# flextimus-prime.net
KiCad netlist of a schematic drawn in EAGLE
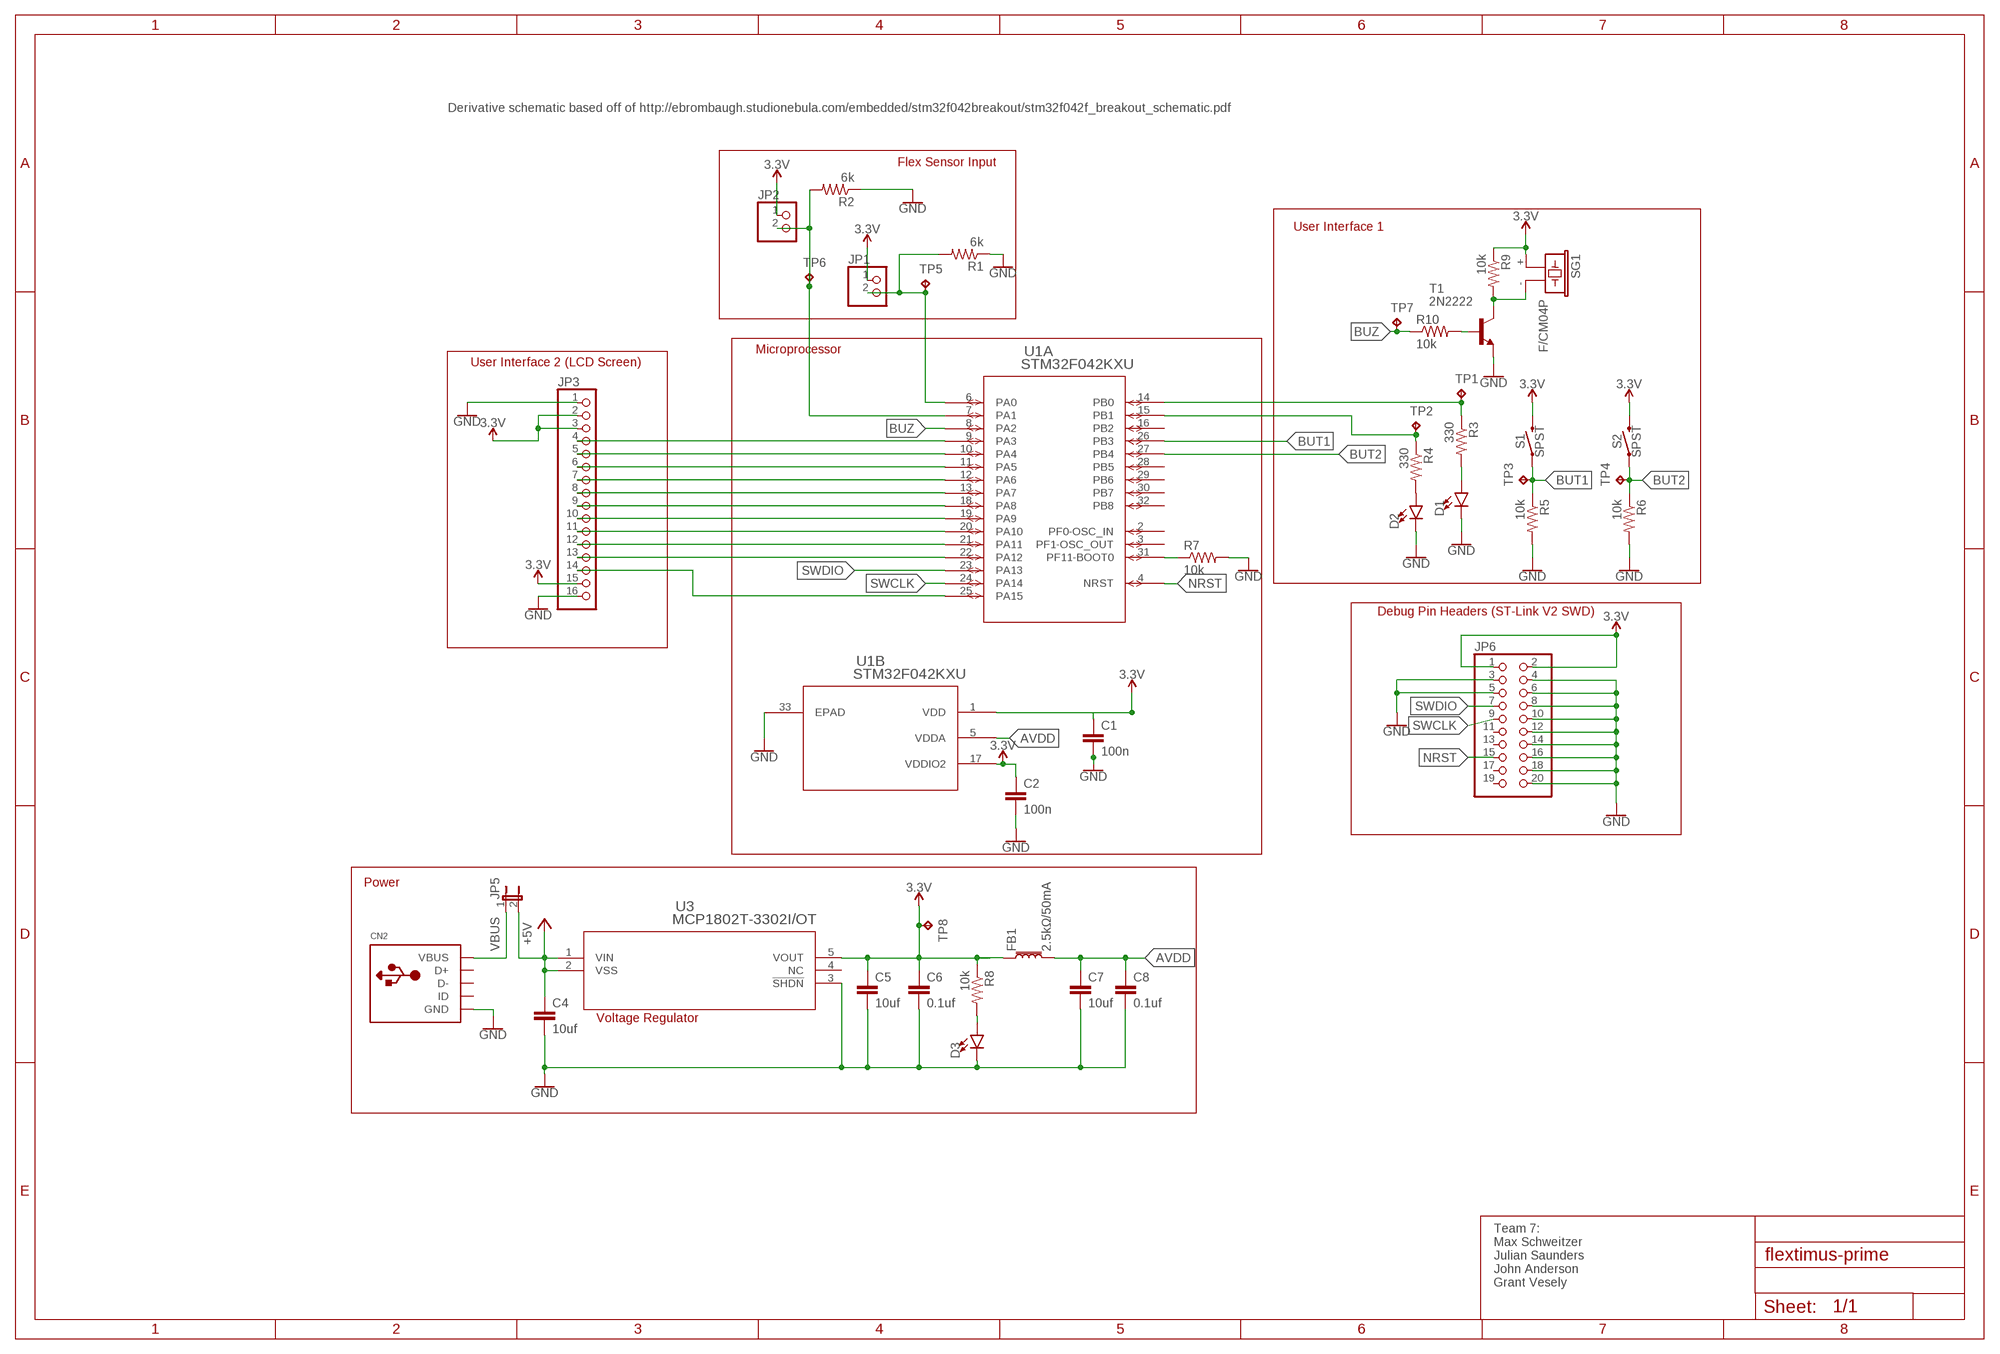
[diagram p0: schematic, sheet 1]

(export (version "E")
  (design (tool "Eeschema 10.0.6"))
  (components
    (comp (ref "C1")
      (value "100n")
      (footprint "eagle-import:C0805")
      (libsource (lib "eagle-import") (part "C-EUC0805"))
    )
    (comp (ref "C2")
      (value "100n")
      (footprint "eagle-import:C0805")
      (libsource (lib "eagle-import") (part "C-EUC0805"))
    )
    (comp (ref "C4")
      (value "10uf")
      (footprint "eagle-import:C0805")
      (libsource (lib "eagle-import") (part "C-EUC0805"))
    )
    (comp (ref "C5")
      (value "10uf")
      (footprint "eagle-import:C0805")
      (libsource (lib "eagle-import") (part "C-EUC0805"))
    )
    (comp (ref "C6")
      (value "0.1uf")
      (footprint "eagle-import:C0805")
      (libsource (lib "eagle-import") (part "C-EUC0805"))
    )
    (comp (ref "C7")
      (value "10uf")
      (footprint "eagle-import:C0805")
      (libsource (lib "eagle-import") (part "C-EUC0805"))
    )
    (comp (ref "C8")
      (value "0.1uf")
      (footprint "eagle-import:C0805")
      (libsource (lib "eagle-import") (part "C-EUC0805"))
    )
    (comp (ref "CN2")
      (value "USBMINIB")
      (footprint "eagle-import:USB-MINIB")
      (libsource (lib "eagle-import") (part "USBMINIB"))
    )
    (comp (ref "D1")
      (value "LED10MM")
      (footprint "eagle-import:LED_10MM")
      (libsource (lib "eagle-import") (part "LED10MM"))
    )
    (comp (ref "D2")
      (value "LED10MM")
      (footprint "eagle-import:LED_10MM")
      (libsource (lib "eagle-import") (part "LED10MM"))
    )
    (comp (ref "D3")
      (value "LED10MM")
      (footprint "eagle-import:LED_10MM")
      (libsource (lib "eagle-import") (part "LED10MM"))
    )
    (comp (ref "FB1")
      (value "2.5kΩ/50mA")
      (footprint "eagle-import:0603")
      (libsource (lib "eagle-import") (part "FERRITE_BEAD-0603"))
    )
    (comp (ref "JP1")
      (value "PINHD-1X2")
      (footprint "eagle-import:1X02")
      (libsource (lib "eagle-import") (part "PINHD-1X2"))
    )
    (comp (ref "JP2")
      (value "PINHD-1X2")
      (footprint "eagle-import:1X02")
      (libsource (lib "eagle-import") (part "PINHD-1X2"))
    )
    (comp (ref "JP3")
      (value "PINHD-1X16")
      (footprint "eagle-import:1X16")
      (libsource (lib "eagle-import") (part "PINHD-1X16"))
    )
    (comp (ref "JP5")
      (value "JP1E")
      (footprint "eagle-import:JP1")
      (libsource (lib "eagle-import") (part "JP1E"))
    )
    (comp (ref "JP6")
      (value "PINHD-2X10")
      (footprint "eagle-import:2X10")
      (libsource (lib "eagle-import") (part "PINHD-2X10"))
    )
    (comp (ref "R1")
      (value "6k")
      (footprint "eagle-import:R0805")
      (libsource (lib "eagle-import") (part "rcl_334_R-US_R0805"))
    )
    (comp (ref "R2")
      (value "6k")
      (footprint "eagle-import:R0805")
      (libsource (lib "eagle-import") (part "rcl_334_R-US_R0805"))
    )
    (comp (ref "R3")
      (value "330")
      (footprint "eagle-import:R0805")
      (libsource (lib "eagle-import") (part "R-US_R0805"))
    )
    (comp (ref "R4")
      (value "330")
      (footprint "eagle-import:R0805")
      (libsource (lib "eagle-import") (part "R-US_R0805"))
    )
    (comp (ref "R5")
      (value "10k")
      (footprint "eagle-import:R0805")
      (libsource (lib "eagle-import") (part "R-US_R0805"))
    )
    (comp (ref "R6")
      (value "10k")
      (footprint "eagle-import:R0805")
      (libsource (lib "eagle-import") (part "R-US_R0805"))
    )
    (comp (ref "R7")
      (value "10k")
      (footprint "eagle-import:R0805")
      (libsource (lib "eagle-import") (part "R-US_R0805"))
    )
    (comp (ref "R8")
      (value "10k")
      (footprint "eagle-import:R0805")
      (libsource (lib "eagle-import") (part "R-US_R0805"))
    )
    (comp (ref "R9")
      (value "10k")
      (footprint "eagle-import:R0805")
      (libsource (lib "eagle-import") (part "R-US_R0805"))
    )
    (comp (ref "R10")
      (value "10k")
      (footprint "eagle-import:R0805")
      (libsource (lib "eagle-import") (part "R-US_R0805"))
    )
    (comp (ref "S1")
      (value "SPST")
      (footprint "eagle-import:TACTILE_SWITCH_PTH_6.0MM")
      (libsource (lib "eagle-import") (part "MOMENTARY-SWITCH-SPST-PTH-6.0MM"))
    )
    (comp (ref "S2")
      (value "SPST")
      (footprint "eagle-import:TACTILE_SWITCH_PTH_6.0MM")
      (libsource (lib "eagle-import") (part "MOMENTARY-SWITCH-SPST-PTH-6.0MM"))
    )
    (comp (ref "SG1")
      (value "F/CM04P")
      (footprint "eagle-import:F_CM04P")
      (libsource (lib "eagle-import") (part "F/CM04P"))
    )
    (comp (ref "T1")
      (value "2N2222")
      (footprint "eagle-import:TO92-EBC-OVAL")
      (libsource (lib "eagle-import") (part "2N2222"))
    )
    (comp (ref "TP1")
      (value "TPB2,54")
      (footprint "eagle-import:B2,54")
      (libsource (lib "eagle-import") (part "TPB2,54"))
    )
    (comp (ref "TP2")
      (value "TPB2,54")
      (footprint "eagle-import:B2,54")
      (libsource (lib "eagle-import") (part "TPB2,54"))
    )
    (comp (ref "TP3")
      (value "TPB2,54")
      (footprint "eagle-import:B2,54")
      (libsource (lib "eagle-import") (part "TPB2,54"))
    )
    (comp (ref "TP4")
      (value "TPB2,54")
      (footprint "eagle-import:B2,54")
      (libsource (lib "eagle-import") (part "TPB2,54"))
    )
    (comp (ref "TP5")
      (value "TPB2,54")
      (footprint "eagle-import:B2,54")
      (libsource (lib "eagle-import") (part "TPB2,54"))
    )
    (comp (ref "TP6")
      (value "TPB2,54")
      (footprint "eagle-import:B2,54")
      (libsource (lib "eagle-import") (part "TPB2,54"))
    )
    (comp (ref "TP7")
      (value "TPB2,54")
      (footprint "eagle-import:B2,54")
      (libsource (lib "eagle-import") (part "TPB2,54"))
    )
    (comp (ref "TP8")
      (value "TPB2,54")
      (footprint "eagle-import:B2,54")
      (libsource (lib "eagle-import") (part "TPB2,54"))
    )
    (comp (ref "U1")
      (value "STM32F042KXU")
      (footprint "eagle-import:UFQFPN32-5X5MM")
      (fields
        (field (name "MANUFACTURER_PART_NUMBER") "stm32f042kxu")
        (field (name "COPYRIGHT") "Copyright C 2016 Accelerated Designs. All rights reserved")
      )
      (libsource (lib "eagle-import") (part "STM32F042KXU"))
    )
    (comp (ref "U3")
      (value "MCP1802T-3302I/OT")
      (footprint "eagle-import:SOT-23-5_MC")
      (fields (field (name "MANUFACTURER_PART_NUMBER") "MCP1802T3302IOT"))
      (libsource (lib "eagle-import") (part "MCP1802T-3302I/OT"))
    )
  )
  (nets
    (net (code "1") (name "+5V") (class "Default")
      (node (ref "C4") (pin "1") (pinfunction "1_1") (pintype "passive"))
      (node (ref "JP5") (pin "2") (pinfunction "2_2") (pintype "passive"))
      (node (ref "U3") (pin "1") (pinfunction "VIN_1") (pintype "passive"))
      (node (ref "U3") (pin "2") (pinfunction "VSS_2") (pintype "passive"))
    )
    (net (code "2") (name "/VBUS") (class "Default")
      (node (ref "CN2") (pin "VBUS") (pinfunction "VBUS_VBUS") (pintype "power_in"))
      (node (ref "JP5") (pin "1") (pinfunction "1_1") (pintype "passive"))
    )
    (net (code "3") (name "3.3V") (class "Default")
      (node (ref "C1") (pin "1") (pinfunction "1_1") (pintype "passive"))
      (node (ref "C2") (pin "1") (pinfunction "1_1") (pintype "passive"))
      (node (ref "C5") (pin "1") (pinfunction "1_1") (pintype "passive"))
      (node (ref "C6") (pin "1") (pinfunction "1_1") (pintype "passive"))
      (node (ref "FB1") (pin "1") (pinfunction "1_1") (pintype "passive"))
      (node (ref "JP1") (pin "1") (pinfunction "1_1") (pintype "passive"))
      (node (ref "JP2") (pin "1") (pinfunction "1_1") (pintype "passive"))
      (node (ref "JP3") (pin "15") (pinfunction "15_15") (pintype "passive"))
      (node (ref "JP3") (pin "2") (pinfunction "2_2") (pintype "passive"))
      (node (ref "JP3") (pin "3") (pinfunction "3_3") (pintype "passive"))
      (node (ref "JP6") (pin "1") (pinfunction "1_1") (pintype "passive"))
      (node (ref "JP6") (pin "2") (pinfunction "2_2") (pintype "passive"))
      (node (ref "R8") (pin "1") (pinfunction "1_1") (pintype "passive"))
      (node (ref "R9") (pin "1") (pinfunction "1_1") (pintype "passive"))
      (node (ref "S1") (pin "3") (pinfunction "2_3") (pintype "passive"))
      (node (ref "S2") (pin "3") (pinfunction "2_3") (pintype "passive"))
      (node (ref "SG1") (pin "+") (pinfunction "1_+") (pintype "passive"))
      (node (ref "TP8") (pin "TP") (pinfunction "TP_TP") (pintype "input"))
      (node (ref "U1") (pin "1") (pinfunction "VDD_1") (pintype "power_in"))
      (node (ref "U1") (pin "17") (pinfunction "VDDIO2_17") (pintype "power_in"))
      (node (ref "U3") (pin "5") (pinfunction "VOUT_5") (pintype "passive"))
    )
    (net (code "4") (name "AVDD") (class "Default")
      (node (ref "C7") (pin "1") (pinfunction "1_1") (pintype "passive"))
      (node (ref "C8") (pin "1") (pinfunction "1_1") (pintype "passive"))
      (node (ref "FB1") (pin "2") (pinfunction "2_2") (pintype "passive"))
      (node (ref "U1") (pin "5") (pinfunction "VDDA_5") (pintype "power_in"))
    )
    (net (code "5") (name "BUT1") (class "Default")
      (node (ref "R5") (pin "1") (pinfunction "1_1") (pintype "passive"))
      (node (ref "S1") (pin "1") (pinfunction "1_1") (pintype "passive"))
      (node (ref "TP3") (pin "TP") (pinfunction "TP_TP") (pintype "input"))
      (node (ref "U1") (pin "26") (pinfunction "PB3_26") (pintype "bidirectional"))
    )
    (net (code "6") (name "BUT2") (class "Default")
      (node (ref "R6") (pin "1") (pinfunction "1_1") (pintype "passive"))
      (node (ref "S2") (pin "1") (pinfunction "1_1") (pintype "passive"))
      (node (ref "TP4") (pin "TP") (pinfunction "TP_TP") (pintype "input"))
      (node (ref "U1") (pin "27") (pinfunction "PB4_27") (pintype "bidirectional"))
    )
    (net (code "7") (name "BUZ") (class "Default")
      (node (ref "R10") (pin "1") (pinfunction "1_1") (pintype "passive"))
      (node (ref "TP7") (pin "TP") (pinfunction "TP_TP") (pintype "input"))
      (node (ref "U1") (pin "8") (pinfunction "PA2_8") (pintype "bidirectional"))
    )
    (net (code "8") (name "GND") (class "Default")
      (node (ref "C1") (pin "2") (pinfunction "2_2") (pintype "passive"))
      (node (ref "C2") (pin "2") (pinfunction "2_2") (pintype "passive"))
      (node (ref "C4") (pin "2") (pinfunction "2_2") (pintype "passive"))
      (node (ref "C5") (pin "2") (pinfunction "2_2") (pintype "passive"))
      (node (ref "C6") (pin "2") (pinfunction "2_2") (pintype "passive"))
      (node (ref "C7") (pin "2") (pinfunction "2_2") (pintype "passive"))
      (node (ref "C8") (pin "2") (pinfunction "2_2") (pintype "passive"))
      (node (ref "CN2") (pin "GND") (pinfunction "GND_GND") (pintype "power_in"))
      (node (ref "D1") (pin "C") (pinfunction "C_C") (pintype "passive"))
      (node (ref "D2") (pin "C") (pinfunction "C_C") (pintype "passive"))
      (node (ref "D3") (pin "C") (pinfunction "C_C") (pintype "passive"))
      (node (ref "JP3") (pin "1") (pinfunction "1_1") (pintype "passive"))
      (node (ref "JP3") (pin "16") (pinfunction "16_16") (pintype "passive"))
      (node (ref "JP6") (pin "10") (pinfunction "10_10") (pintype "passive"))
      (node (ref "JP6") (pin "12") (pinfunction "12_12") (pintype "passive"))
      (node (ref "JP6") (pin "14") (pinfunction "14_14") (pintype "passive"))
      (node (ref "JP6") (pin "16") (pinfunction "16_16") (pintype "passive"))
      (node (ref "JP6") (pin "18") (pinfunction "18_18") (pintype "passive"))
      (node (ref "JP6") (pin "20") (pinfunction "20_20") (pintype "passive"))
      (node (ref "JP6") (pin "3") (pinfunction "3_3") (pintype "passive"))
      (node (ref "JP6") (pin "4") (pinfunction "4_4") (pintype "passive"))
      (node (ref "JP6") (pin "5") (pinfunction "5_5") (pintype "passive"))
      (node (ref "JP6") (pin "6") (pinfunction "6_6") (pintype "passive"))
      (node (ref "JP6") (pin "8") (pinfunction "8_8") (pintype "passive"))
      (node (ref "R1") (pin "1") (pinfunction "1_1") (pintype "passive"))
      (node (ref "R2") (pin "1") (pinfunction "1_1") (pintype "passive"))
      (node (ref "R5") (pin "2") (pinfunction "2_2") (pintype "passive"))
      (node (ref "R6") (pin "2") (pinfunction "2_2") (pintype "passive"))
      (node (ref "R7") (pin "2") (pinfunction "2_2") (pintype "passive"))
      (node (ref "T1") (pin "E") (pinfunction "E_E") (pintype "passive"))
      (node (ref "U1") (pin "33") (pinfunction "EPAD_33") (pintype "passive"))
      (node (ref "U3") (pin "3") (pinfunction "~{SHDN}_3") (pintype "passive"))
    )
    (net (code "9") (name "NRST") (class "Default")
      (node (ref "JP6") (pin "15") (pinfunction "15_15") (pintype "passive"))
      (node (ref "U1") (pin "4") (pinfunction "NRST_4") (pintype "bidirectional"))
    )
    (net (code "10") (name "Net-(D1-PadA)") (class "Default")
      (node (ref "D1") (pin "A") (pinfunction "A_A") (pintype "passive"))
      (node (ref "R3") (pin "2") (pinfunction "2_2") (pintype "passive"))
    )
    (net (code "11") (name "Net-(D2-PadA)") (class "Default")
      (node (ref "D2") (pin "A") (pinfunction "A_A") (pintype "passive"))
      (node (ref "R4") (pin "2") (pinfunction "2_2") (pintype "passive"))
    )
    (net (code "12") (name "Net-(D3-PadA)") (class "Default")
      (node (ref "D3") (pin "A") (pinfunction "A_A") (pintype "passive"))
      (node (ref "R8") (pin "2") (pinfunction "2_2") (pintype "passive"))
    )
    (net (code "13") (name "Net-(R10-Pad2)") (class "Default")
      (node (ref "R10") (pin "2") (pinfunction "2_2") (pintype "passive"))
      (node (ref "T1") (pin "B") (pinfunction "B_B") (pintype "passive"))
    )
    (net (code "14") (name "Net-(SG1-2)") (class "Default")
      (node (ref "R9") (pin "2") (pinfunction "2_2") (pintype "passive"))
      (node (ref "SG1") (pin "-") (pinfunction "2_-") (pintype "passive"))
      (node (ref "T1") (pin "C") (pinfunction "C_C") (pintype "passive"))
    )
    (net (code "15") (name "Net-(U1A-PA0)") (class "Default")
      (node (ref "JP1") (pin "2") (pinfunction "2_2") (pintype "passive"))
      (node (ref "R1") (pin "2") (pinfunction "2_2") (pintype "passive"))
      (node (ref "TP5") (pin "TP") (pinfunction "TP_TP") (pintype "input"))
      (node (ref "U1") (pin "6") (pinfunction "PA0_6") (pintype "bidirectional"))
    )
    (net (code "16") (name "Net-(U1A-PA1)") (class "Default")
      (node (ref "JP2") (pin "2") (pinfunction "2_2") (pintype "passive"))
      (node (ref "R2") (pin "2") (pinfunction "2_2") (pintype "passive"))
      (node (ref "TP6") (pin "TP") (pinfunction "TP_TP") (pintype "input"))
      (node (ref "U1") (pin "7") (pinfunction "PA1_7") (pintype "bidirectional"))
    )
    (net (code "17") (name "Net-(U1A-PA3)") (class "Default")
      (node (ref "JP3") (pin "4") (pinfunction "4_4") (pintype "passive"))
      (node (ref "U1") (pin "9") (pinfunction "PA3_9") (pintype "bidirectional"))
    )
    (net (code "18") (name "Net-(U1A-PA4)") (class "Default")
      (node (ref "JP3") (pin "5") (pinfunction "5_5") (pintype "passive"))
      (node (ref "U1") (pin "10") (pinfunction "PA4_10") (pintype "bidirectional"))
    )
    (net (code "19") (name "Net-(U1A-PA5)") (class "Default")
      (node (ref "JP3") (pin "6") (pinfunction "6_6") (pintype "passive"))
      (node (ref "U1") (pin "11") (pinfunction "PA5_11") (pintype "bidirectional"))
    )
    (net (code "20") (name "Net-(U1A-PA6)") (class "Default")
      (node (ref "JP3") (pin "7") (pinfunction "7_7") (pintype "passive"))
      (node (ref "U1") (pin "12") (pinfunction "PA6_12") (pintype "bidirectional"))
    )
    (net (code "21") (name "Net-(U1A-PA7)") (class "Default")
      (node (ref "JP3") (pin "8") (pinfunction "8_8") (pintype "passive"))
      (node (ref "U1") (pin "13") (pinfunction "PA7_13") (pintype "bidirectional"))
    )
    (net (code "22") (name "Net-(U1A-PA8)") (class "Default")
      (node (ref "JP3") (pin "9") (pinfunction "9_9") (pintype "passive"))
      (node (ref "U1") (pin "18") (pinfunction "PA8_18") (pintype "bidirectional"))
    )
    (net (code "23") (name "Net-(U1A-PA9)") (class "Default")
      (node (ref "JP3") (pin "10") (pinfunction "10_10") (pintype "passive"))
      (node (ref "U1") (pin "19") (pinfunction "PA9_19") (pintype "bidirectional"))
    )
    (net (code "24") (name "Net-(U1A-PA10)") (class "Default")
      (node (ref "JP3") (pin "11") (pinfunction "11_11") (pintype "passive"))
      (node (ref "U1") (pin "20") (pinfunction "PA10_20") (pintype "bidirectional"))
    )
    (net (code "25") (name "Net-(U1A-PA11)") (class "Default")
      (node (ref "JP3") (pin "12") (pinfunction "12_12") (pintype "passive"))
      (node (ref "U1") (pin "21") (pinfunction "PA11_21") (pintype "bidirectional"))
    )
    (net (code "26") (name "Net-(U1A-PA12)") (class "Default")
      (node (ref "JP3") (pin "13") (pinfunction "13_13") (pintype "passive"))
      (node (ref "U1") (pin "22") (pinfunction "PA12_22") (pintype "bidirectional"))
    )
    (net (code "27") (name "Net-(U1A-PA15)") (class "Default")
      (node (ref "JP3") (pin "14") (pinfunction "14_14") (pintype "passive"))
      (node (ref "U1") (pin "25") (pinfunction "PA15_25") (pintype "bidirectional"))
    )
    (net (code "28") (name "Net-(U1A-PB0)") (class "Default")
      (node (ref "R3") (pin "1") (pinfunction "1_1") (pintype "passive"))
      (node (ref "TP1") (pin "TP") (pinfunction "TP_TP") (pintype "input"))
      (node (ref "U1") (pin "14") (pinfunction "PB0_14") (pintype "bidirectional"))
    )
    (net (code "29") (name "Net-(U1A-PB1)") (class "Default")
      (node (ref "R4") (pin "1") (pinfunction "1_1") (pintype "passive"))
      (node (ref "TP2") (pin "TP") (pinfunction "TP_TP") (pintype "input"))
      (node (ref "U1") (pin "15") (pinfunction "PB1_15") (pintype "bidirectional"))
    )
    (net (code "30") (name "Net-(U1A-PF11-BOOT0)") (class "Default")
      (node (ref "R7") (pin "1") (pinfunction "1_1") (pintype "passive"))
      (node (ref "U1") (pin "31") (pinfunction "PF11-BOOT0_31") (pintype "bidirectional"))
    )
    (net (code "31") (name "SWCLK") (class "Default")
      (node (ref "JP6") (pin "9") (pinfunction "9_9") (pintype "passive"))
      (node (ref "U1") (pin "24") (pinfunction "PA14_24") (pintype "bidirectional"))
    )
    (net (code "32") (name "SWDIO") (class "Default")
      (node (ref "JP6") (pin "7") (pinfunction "7_7") (pintype "passive"))
      (node (ref "U1") (pin "23") (pinfunction "PA13_23") (pintype "bidirectional"))
    )
    (net (code "33") (name "unconnected-(CN2-PadD+)") (class "Default")
      (node (ref "CN2") (pin "D+") (pinfunction "D+_D+") (pintype "bidirectional"))
    )
    (net (code "34") (name "unconnected-(CN2-PadD-)") (class "Default")
      (node (ref "CN2") (pin "D-") (pinfunction "D-_D-") (pintype "bidirectional"))
    )
    (net (code "35") (name "unconnected-(CN2-PadID)") (class "Default")
      (node (ref "CN2") (pin "ID") (pinfunction "ID_ID") (pintype "bidirectional"))
    )
    (net (code "36") (name "unconnected-(JP6-Pad11)") (class "Default")
      (node (ref "JP6") (pin "11") (pinfunction "11_11") (pintype "passive"))
    )
    (net (code "37") (name "unconnected-(JP6-Pad13)") (class "Default")
      (node (ref "JP6") (pin "13") (pinfunction "13_13") (pintype "passive"))
    )
    (net (code "38") (name "unconnected-(JP6-Pad17)") (class "Default")
      (node (ref "JP6") (pin "17") (pinfunction "17_17") (pintype "passive"))
    )
    (net (code "39") (name "unconnected-(JP6-Pad19)") (class "Default")
      (node (ref "JP6") (pin "19") (pinfunction "19_19") (pintype "passive"))
    )
    (net (code "40") (name "unconnected-(U1A-PB2-Pad16)") (class "Default")
      (node (ref "U1") (pin "16") (pinfunction "PB2_16") (pintype "bidirectional"))
    )
    (net (code "41") (name "unconnected-(U1A-PB5-Pad28)") (class "Default")
      (node (ref "U1") (pin "28") (pinfunction "PB5_28") (pintype "bidirectional"))
    )
    (net (code "42") (name "unconnected-(U1A-PB6-Pad29)") (class "Default")
      (node (ref "U1") (pin "29") (pinfunction "PB6_29") (pintype "bidirectional"))
    )
    (net (code "43") (name "unconnected-(U1A-PB7-Pad30)") (class "Default")
      (node (ref "U1") (pin "30") (pinfunction "PB7_30") (pintype "bidirectional"))
    )
    (net (code "44") (name "unconnected-(U1A-PB8-Pad32)") (class "Default")
      (node (ref "U1") (pin "32") (pinfunction "PB8_32") (pintype "bidirectional"))
    )
    (net (code "45") (name "unconnected-(U1A-PF0-OSC_IN-Pad2)") (class "Default")
      (node (ref "U1") (pin "2") (pinfunction "PF0-OSC_IN_2") (pintype "bidirectional"))
    )
    (net (code "46") (name "unconnected-(U1A-PF1-OSC_OUT-Pad3)") (class "Default")
      (node (ref "U1") (pin "3") (pinfunction "PF1-OSC_OUT_3") (pintype "bidirectional"))
    )
    (net (code "47") (name "unconnected-(U3-NC-Pad4)") (class "Default")
      (node (ref "U3") (pin "4") (pinfunction "NC_4") (pintype "passive"))
    )
  )
)
